# Sch_PowerSupply.net
KiCad netlist of a schematic drawn in EAGLE
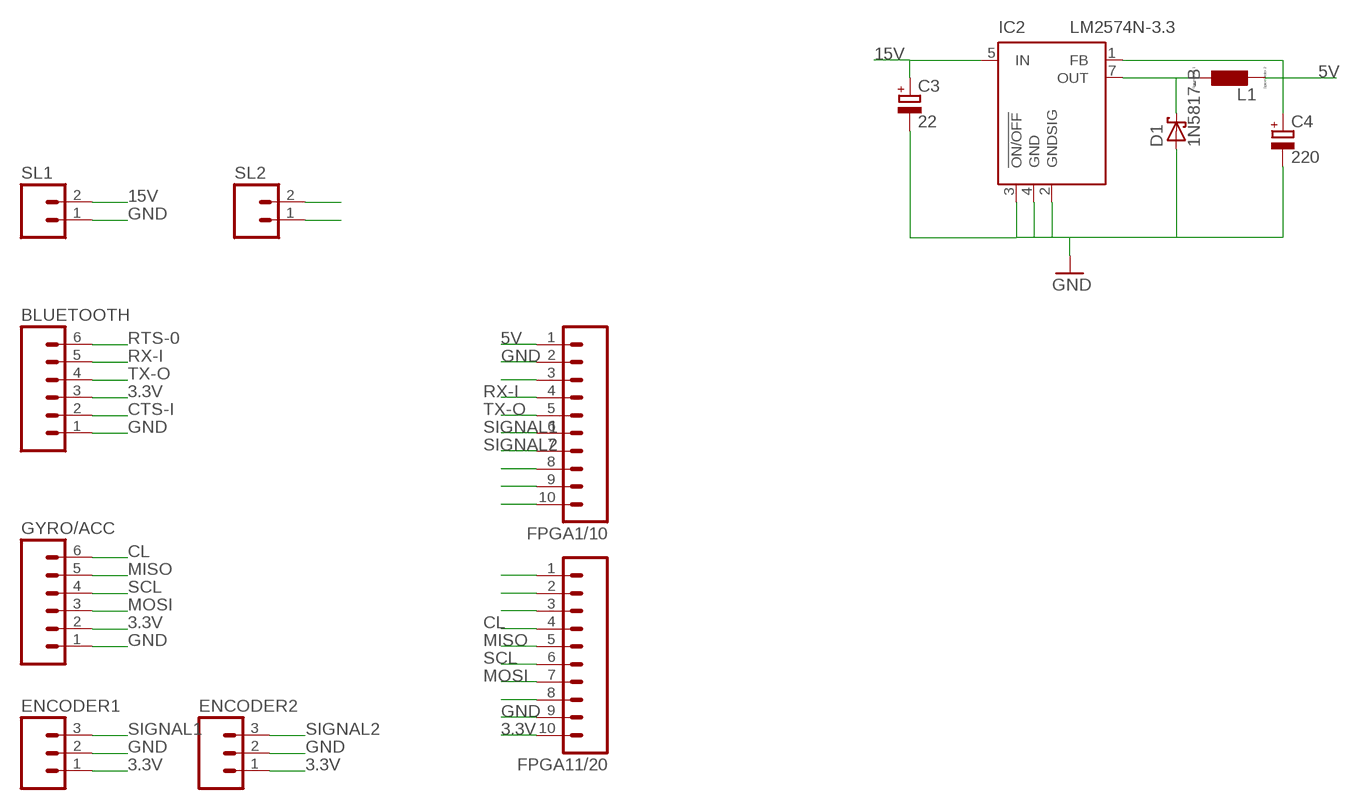
[diagram p0: schematic, sheet 1]

(export (version "E")
  (design (tool "Eeschema 10.0.6"))
  (components
    (comp (ref "BLUETOOTH")
      (value "M06")
      (footprint "eagle-import:06P")
      (libsource (lib "eagle-import") (part "M06"))
    )
    (comp (ref "C3")
      (value "22")
      (footprint "eagle-import:E5-8,5")
      (libsource (lib "eagle-import") (part "CPOL-EUE5-8.5"))
    )
    (comp (ref "C4")
      (value "220")
      (footprint "eagle-import:E5-8,5")
      (libsource (lib "eagle-import") (part "CPOL-EUE5-8.5"))
    )
    (comp (ref "D1")
      (value "1N5817-B")
      (footprint "eagle-import:DO41-7.6")
      (libsource (lib "eagle-import") (part "1N5817-B"))
    )
    (comp (ref "ENCODER1")
      (value "M03")
      (footprint "eagle-import:03P")
      (libsource (lib "eagle-import") (part "M03"))
    )
    (comp (ref "ENCODER2")
      (value "M03")
      (footprint "eagle-import:03P")
      (libsource (lib "eagle-import") (part "M03"))
    )
    (comp (ref "FPGA1/10")
      (value "M10")
      (footprint "eagle-import:10P")
      (libsource (lib "eagle-import") (part "M10"))
    )
    (comp (ref "FPGA11/20")
      (value "M10")
      (footprint "eagle-import:10P")
      (libsource (lib "eagle-import") (part "M10"))
    )
    (comp (ref "GYRO/ACC")
      (value "M06")
      (footprint "eagle-import:06P")
      (libsource (lib "eagle-import") (part "M06"))
    )
    (comp (ref "IC2")
      (value "LM2574N-3.3")
      (footprint "eagle-import:DIL08")
      (libsource (lib "eagle-import") (part "LM2574?-N3.3"))
    )
    (comp (ref "L1")
      (value "L0204/7")
      (footprint "eagle-import:0204_7")
      (libsource (lib "eagle-import") (part "L0204/7"))
    )
    (comp (ref "SL1")
      (value "M02")
      (footprint "eagle-import:02P")
      (libsource (lib "eagle-import") (part "M02"))
    )
    (comp (ref "SL2")
      (value "M02")
      (footprint "eagle-import:02P")
      (libsource (lib "eagle-import") (part "M02"))
    )
  )
  (nets
    (net (code "1") (name "/3.3V") (class "Default")
      (node (ref "BLUETOOTH") (pin "3") (pinfunction "3_3") (pintype "passive"))
      (node (ref "ENCODER1") (pin "1") (pinfunction "1_1") (pintype "passive"))
      (node (ref "ENCODER2") (pin "1") (pinfunction "1_1") (pintype "passive"))
      (node (ref "FPGA11/20") (pin "10") (pinfunction "10_10") (pintype "passive"))
      (node (ref "GYRO/ACC") (pin "2") (pinfunction "2_2") (pintype "passive"))
    )
    (net (code "2") (name "/5V") (class "Default")
      (node (ref "C4") (pin "+") (pinfunction "+_+") (pintype "passive"))
      (node (ref "FPGA1/10") (pin "1") (pinfunction "1_1") (pintype "passive"))
      (node (ref "IC2") (pin "1") (pinfunction "FB_1") (pintype "input"))
      (node (ref "L1") (pin "2") (pinfunction "2_2") (pintype "passive"))
      (node (ref "SL2") (pin "2") (pinfunction "2_2") (pintype "passive"))
    )
    (net (code "3") (name "/15V") (class "Default")
      (node (ref "C3") (pin "+") (pinfunction "+_+") (pintype "passive"))
      (node (ref "IC2") (pin "5") (pinfunction "IN_5") (pintype "input"))
      (node (ref "SL1") (pin "2") (pinfunction "2_2") (pintype "passive"))
    )
    (net (code "4") (name "/CL") (class "Default")
      (node (ref "FPGA11/20") (pin "4") (pinfunction "4_4") (pintype "passive"))
      (node (ref "GYRO/ACC") (pin "6") (pinfunction "6_6") (pintype "passive"))
    )
    (net (code "5") (name "/CTS-I") (class "Default")
      (node (ref "BLUETOOTH") (pin "2") (pinfunction "2_2") (pintype "passive"))
    )
    (net (code "6") (name "/MISO") (class "Default")
      (node (ref "FPGA11/20") (pin "5") (pinfunction "5_5") (pintype "passive"))
      (node (ref "GYRO/ACC") (pin "5") (pinfunction "5_5") (pintype "passive"))
    )
    (net (code "7") (name "/MOSI") (class "Default")
      (node (ref "FPGA11/20") (pin "7") (pinfunction "7_7") (pintype "passive"))
      (node (ref "GYRO/ACC") (pin "3") (pinfunction "3_3") (pintype "passive"))
    )
    (net (code "8") (name "/RTS-0") (class "Default")
      (node (ref "BLUETOOTH") (pin "6") (pinfunction "6_6") (pintype "passive"))
    )
    (net (code "9") (name "/RX-I") (class "Default")
      (node (ref "BLUETOOTH") (pin "5") (pinfunction "5_5") (pintype "passive"))
      (node (ref "FPGA1/10") (pin "4") (pinfunction "4_4") (pintype "passive"))
    )
    (net (code "10") (name "/SCL") (class "Default")
      (node (ref "FPGA11/20") (pin "6") (pinfunction "6_6") (pintype "passive"))
      (node (ref "GYRO/ACC") (pin "4") (pinfunction "4_4") (pintype "passive"))
    )
    (net (code "11") (name "/SIGNAL1") (class "Default")
      (node (ref "ENCODER1") (pin "3") (pinfunction "3_3") (pintype "passive"))
      (node (ref "FPGA1/10") (pin "6") (pinfunction "6_6") (pintype "passive"))
    )
    (net (code "12") (name "/SIGNAL2") (class "Default")
      (node (ref "ENCODER2") (pin "3") (pinfunction "3_3") (pintype "passive"))
      (node (ref "FPGA1/10") (pin "7") (pinfunction "7_7") (pintype "passive"))
    )
    (net (code "13") (name "/TX-O") (class "Default")
      (node (ref "BLUETOOTH") (pin "4") (pinfunction "4_4") (pintype "passive"))
      (node (ref "FPGA1/10") (pin "5") (pinfunction "5_5") (pintype "passive"))
    )
    (net (code "14") (name "GND") (class "Default")
      (node (ref "BLUETOOTH") (pin "1") (pinfunction "1_1") (pintype "passive"))
      (node (ref "C3") (pin "-") (pinfunction "-_-") (pintype "passive"))
      (node (ref "C4") (pin "-") (pinfunction "-_-") (pintype "passive"))
      (node (ref "D1") (pin "A") (pinfunction "A_A") (pintype "passive"))
      (node (ref "ENCODER1") (pin "2") (pinfunction "2_2") (pintype "passive"))
      (node (ref "ENCODER2") (pin "2") (pinfunction "2_2") (pintype "passive"))
      (node (ref "FPGA1/10") (pin "2") (pinfunction "2_2") (pintype "passive"))
      (node (ref "FPGA11/20") (pin "9") (pinfunction "9_9") (pintype "passive"))
      (node (ref "GYRO/ACC") (pin "1") (pinfunction "1_1") (pintype "passive"))
      (node (ref "IC2") (pin "2") (pinfunction "GNDSIG_2") (pintype "input"))
      (node (ref "IC2") (pin "3") (pinfunction "~{ON/OFF}_3") (pintype "input"))
      (node (ref "IC2") (pin "4") (pinfunction "GND_4") (pintype "power_in"))
      (node (ref "SL1") (pin "1") (pinfunction "1_1") (pintype "passive"))
      (node (ref "SL2") (pin "1") (pinfunction "1_1") (pintype "passive"))
    )
    (net (code "15") (name "Net-(IC2-OUT)") (class "Default")
      (node (ref "D1") (pin "C") (pinfunction "C_C") (pintype "passive"))
      (node (ref "IC2") (pin "7") (pinfunction "OUT_7") (pintype "passive"))
      (node (ref "L1") (pin "1") (pinfunction "1_1") (pintype "passive"))
    )
    (net (code "16") (name "unconnected-(FPGA1/10-Pad3)") (class "Default")
      (node (ref "FPGA1/10") (pin "3") (pinfunction "3_3") (pintype "passive"))
    )
    (net (code "17") (name "unconnected-(FPGA1/10-Pad8)") (class "Default")
      (node (ref "FPGA1/10") (pin "8") (pinfunction "8_8") (pintype "passive"))
    )
    (net (code "18") (name "unconnected-(FPGA1/10-Pad9)") (class "Default")
      (node (ref "FPGA1/10") (pin "9") (pinfunction "9_9") (pintype "passive"))
    )
    (net (code "19") (name "unconnected-(FPGA1/10-Pad10)") (class "Default")
      (node (ref "FPGA1/10") (pin "10") (pinfunction "10_10") (pintype "passive"))
    )
    (net (code "20") (name "unconnected-(FPGA11/20-Pad1)") (class "Default")
      (node (ref "FPGA11/20") (pin "1") (pinfunction "1_1") (pintype "passive"))
    )
    (net (code "21") (name "unconnected-(FPGA11/20-Pad2)") (class "Default")
      (node (ref "FPGA11/20") (pin "2") (pinfunction "2_2") (pintype "passive"))
    )
    (net (code "22") (name "unconnected-(FPGA11/20-Pad3)") (class "Default")
      (node (ref "FPGA11/20") (pin "3") (pinfunction "3_3") (pintype "passive"))
    )
    (net (code "23") (name "unconnected-(FPGA11/20-Pad8)") (class "Default")
      (node (ref "FPGA11/20") (pin "8") (pinfunction "8_8") (pintype "passive"))
    )
  )
)
